# J2-1xGTHQ_L_1xGTHCLK_GTRQ_2xGTRCLK_4xPLL.net
KiCad netlist of a schematic drawn in Altium Designer
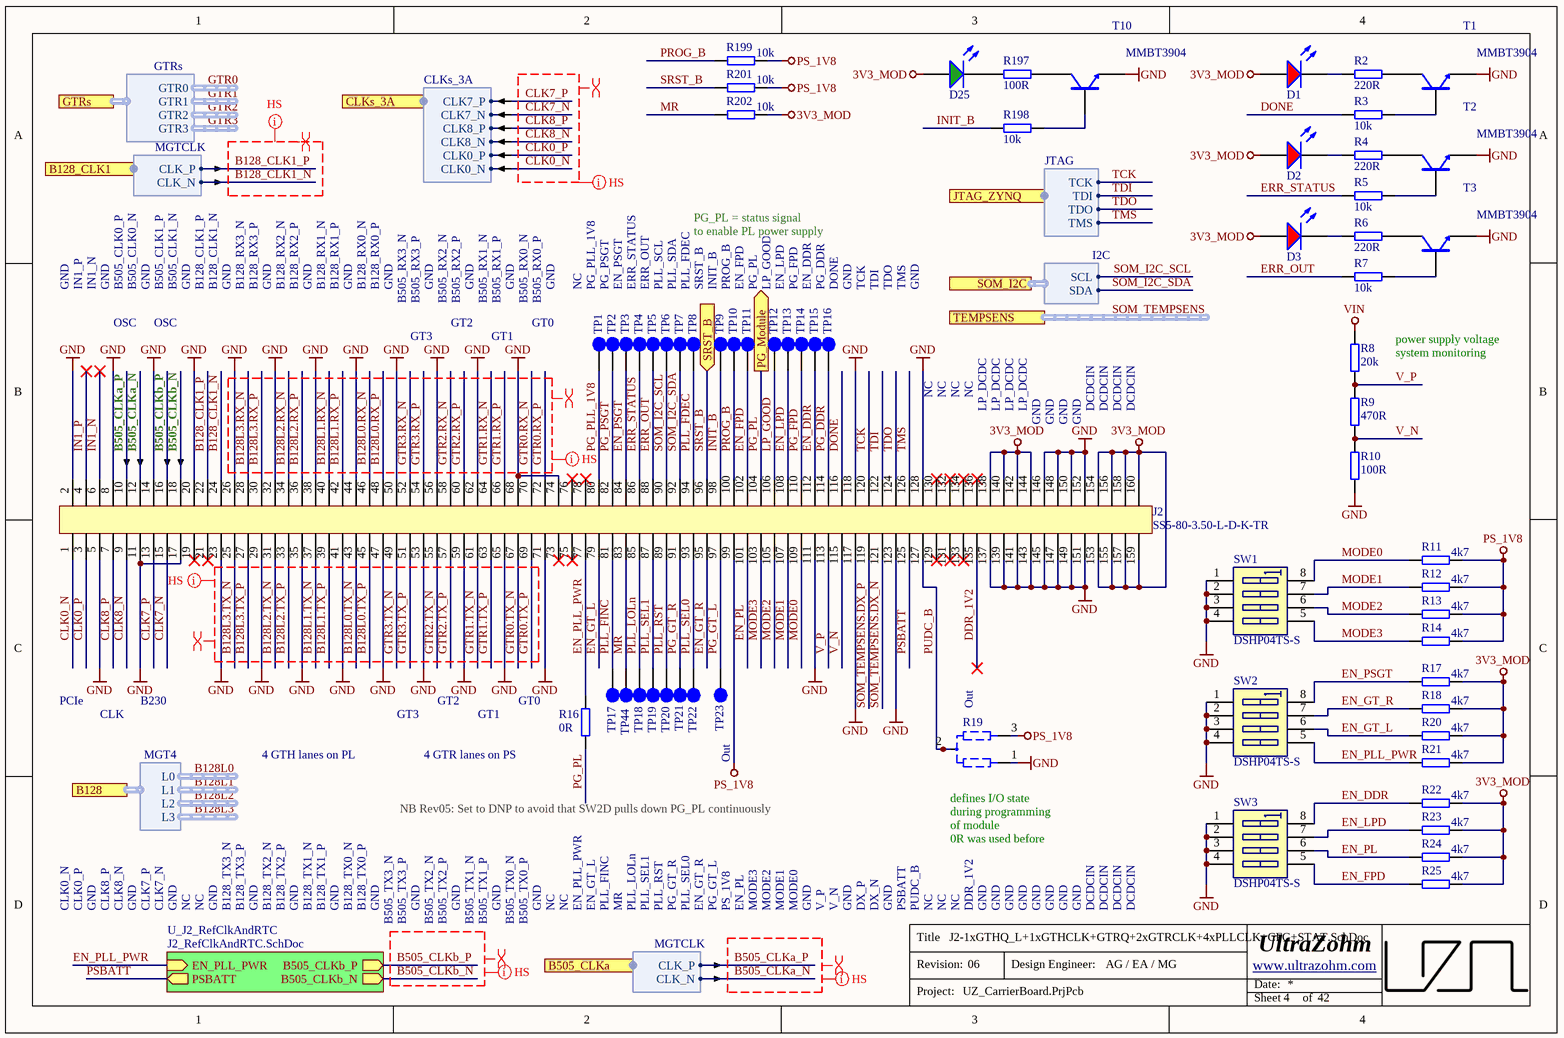
[diagram p0: J2-1xGTHQ_L+1xGTHCLK+GTRQ+2xGTRCLK+4xPLLCLK+CFG+STAT.SchDoc]

(export (version "E")
  (design (tool "Eeschema 10.0.6"))
  (components
    (comp (ref "D1")
      (value "LED Red")
      (footprint "WL-SMCW_0603")
      (description "Standard LEDs - SMD 0603 red")
      (fields
        (field (name "MANUFACTURER PART NUMBER") "UZgen_LED_0603_Red")
        (field (name "MANUFACTURER") "UZgen")
        (field (name "CREATED FROM") "UZgenTool")
      )
      (libsource (lib "user") (part "LED_Red"))
    )
    (comp (ref "D2")
      (value "LED Red")
      (footprint "WL-SMCW_0603")
      (description "Standard LEDs - SMD 0603 red")
      (fields
        (field (name "MANUFACTURER PART NUMBER") "UZgen_LED_0603_Red")
        (field (name "MANUFACTURER") "UZgen")
        (field (name "CREATED FROM") "UZgenTool")
      )
      (libsource (lib "user") (part "LED_Red"))
    )
    (comp (ref "D3")
      (value "LED Red")
      (footprint "WL-SMCW_0603")
      (description "Standard LEDs - SMD 0603 red")
      (fields
        (field (name "MANUFACTURER PART NUMBER") "UZgen_LED_0603_Red")
        (field (name "MANUFACTURER") "UZgen")
        (field (name "CREATED FROM") "UZgenTool")
      )
      (libsource (lib "user") (part "LED_Red"))
    )
    (comp (ref "D25")
      (value "LED Green")
      (footprint "WL-SMCW_0603")
      (description "Standard LEDs - SMD 0603 green")
      (fields
        (field (name "MANUFACTURER PART NUMBER") "UZgen_LED_0603_Green")
        (field (name "MANUFACTURER") "UZgen")
        (field (name "CREATED FROM") "UZgenTool")
      )
      (libsource (lib "user") (part "LED_Green"))
    )
    (comp (ref "J2")
      (value "SS5-80-3.50-L-D-K-TR")
      (footprint "SS5-80-3.50-L-D-K-TR")
      (description "0.5 mm Ultra Fine Pitch Socket REF192552-01, 160 Pins")
      (fields
        (field (name "MANUFACTURER") "SAMTEC")
        (field (name "LCSC PART NUMBER") "C5292077")
        (field (name "CREATED FROM") "MGremer")
      )
      (libsource (lib "user") (part "SS5-80-3.50-L-D-K-TR"))
    )
    (comp (ref "R2")
      (value "220R")
      (footprint "R_0603_TE")
      (description "Generic resistor")
      (fields
        (field (name "TOLERANCE") "1 %")
        (field (name "MANUFACTURER PART NUMBER") "UZgen_R_0603_220R")
        (field (name "CREATED FROM") "UZgenTool")
      )
      (libsource (lib "user") (part "RES"))
    )
    (comp (ref "R3")
      (value "10k")
      (footprint "R_0603_TE")
      (description "Generic resistor")
      (fields
        (field (name "TOLERANCE") "1 %")
        (field (name "MANUFACTURER PART NUMBER") "UZgen_R_0603_10k")
        (field (name "CREATED FROM") "AGeiger")
      )
      (libsource (lib "user") (part "RES"))
    )
    (comp (ref "R4")
      (value "220R")
      (footprint "R_0603_TE")
      (description "Generic resistor")
      (fields
        (field (name "TOLERANCE") "1 %")
        (field (name "MANUFACTURER PART NUMBER") "UZgen_R_0603_220R")
        (field (name "CREATED FROM") "UZgenTool")
      )
      (libsource (lib "user") (part "RES"))
    )
    (comp (ref "R5")
      (value "10k")
      (footprint "R_0603_TE")
      (description "Generic resistor")
      (fields
        (field (name "TOLERANCE") "1 %")
        (field (name "MANUFACTURER PART NUMBER") "UZgen_R_0603_10k")
        (field (name "CREATED FROM") "AGeiger")
      )
      (libsource (lib "user") (part "RES"))
    )
    (comp (ref "R6")
      (value "220R")
      (footprint "R_0603_TE")
      (description "Generic resistor")
      (fields
        (field (name "TOLERANCE") "1 %")
        (field (name "MANUFACTURER PART NUMBER") "UZgen_R_0603_220R")
        (field (name "CREATED FROM") "UZgenTool")
      )
      (libsource (lib "user") (part "RES"))
    )
    (comp (ref "R7")
      (value "10k")
      (footprint "R_0603_TE")
      (description "Generic resistor")
      (fields
        (field (name "TOLERANCE") "1 %")
        (field (name "MANUFACTURER PART NUMBER") "UZgen_R_0603_10k")
        (field (name "CREATED FROM") "AGeiger")
      )
      (libsource (lib "user") (part "RES"))
    )
    (comp (ref "R8")
      (value "20k")
      (footprint "R_0603_TE")
      (description "Generic resistor")
      (fields
        (field (name "TOLERANCE") "1 %")
        (field (name "MANUFACTURER PART NUMBER") "UZgen_R_0603_20k")
        (field (name "CREATED FROM") "UZgenTool")
      )
      (libsource (lib "user") (part "RES"))
    )
    (comp (ref "R9")
      (value "470R")
      (footprint "R_0603_TE")
      (description "Generic resistor")
      (fields
        (field (name "TOLERANCE") "1 %")
        (field (name "MANUFACTURER PART NUMBER") "UZgen_R_0603_470R")
        (field (name "CREATED FROM") "UZgenTool")
      )
      (libsource (lib "user") (part "RES"))
    )
    (comp (ref "R10")
      (value "100R")
      (footprint "R_0603_TE")
      (description "Generic resistor")
      (fields
        (field (name "TOLERANCE") "1 %")
        (field (name "MANUFACTURER PART NUMBER") "UZgen_R_0603_100R")
        (field (name "CREATED FROM") "UZgenTool")
      )
      (libsource (lib "user") (part "RES"))
    )
    (comp (ref "R11")
      (value "4k7")
      (footprint "R_0603_TE")
      (description "Generic resistor")
      (fields
        (field (name "TOLERANCE") "1 %")
        (field (name "MANUFACTURER PART NUMBER") "UZgen_R_0603_4k7")
        (field (name "CREATED FROM") "UZgenTool")
      )
      (libsource (lib "user") (part "RES"))
    )
    (comp (ref "R12")
      (value "4k7")
      (footprint "R_0603_TE")
      (description "Generic resistor")
      (fields
        (field (name "TOLERANCE") "1 %")
        (field (name "MANUFACTURER PART NUMBER") "UZgen_R_0603_4k7")
        (field (name "CREATED FROM") "UZgenTool")
      )
      (libsource (lib "user") (part "RES"))
    )
    (comp (ref "R13")
      (value "4k7")
      (footprint "R_0603_TE")
      (description "Generic resistor")
      (fields
        (field (name "TOLERANCE") "1 %")
        (field (name "MANUFACTURER PART NUMBER") "UZgen_R_0603_4k7")
        (field (name "CREATED FROM") "UZgenTool")
      )
      (libsource (lib "user") (part "RES"))
    )
    (comp (ref "R14")
      (value "4k7")
      (footprint "R_0603_TE")
      (description "Generic resistor")
      (fields
        (field (name "TOLERANCE") "1 %")
        (field (name "MANUFACTURER PART NUMBER") "UZgen_R_0603_4k7")
        (field (name "CREATED FROM") "UZgenTool")
      )
      (libsource (lib "user") (part "RES"))
    )
    (comp (ref "R16")
      (value "0R")
      (footprint "R_0603_TE")
      (description "Generic resistor")
      (fields
        (field (name "TOLERANCE") "1 %")
        (field (name "MANUFACTURER PART NUMBER") "UZgen_R_0603_0R")
        (field (name "CREATED FROM") "UZgenTool")
      )
      (libsource (lib "user") (part "RES"))
    )
    (comp (ref "R17")
      (value "4k7")
      (footprint "R_0603_TE")
      (description "Generic resistor")
      (fields
        (field (name "TOLERANCE") "1 %")
        (field (name "MANUFACTURER PART NUMBER") "UZgen_R_0603_4k7")
        (field (name "CREATED FROM") "UZgenTool")
      )
      (libsource (lib "user") (part "RES"))
    )
    (comp (ref "R18")
      (value "4k7")
      (footprint "R_0603_TE")
      (description "Generic resistor")
      (fields
        (field (name "TOLERANCE") "1 %")
        (field (name "MANUFACTURER PART NUMBER") "UZgen_R_0603_4k7")
        (field (name "CREATED FROM") "UZgenTool")
      )
      (libsource (lib "user") (part "RES"))
    )
    (comp (ref "R19")
      (value "Manual Assembly 1608 (0603)")
      (footprint "TP_DUAL_RES_0603")
      (description "Manual Assembly Resistors Placeholder 1608 (0603) Dual")
      (libsource (lib "TE") (part "TP_DUAL_RES_0603"))
    )
    (comp (ref "R20")
      (value "4k7")
      (footprint "R_0603_TE")
      (description "Generic resistor")
      (fields
        (field (name "TOLERANCE") "1 %")
        (field (name "MANUFACTURER PART NUMBER") "UZgen_R_0603_4k7")
        (field (name "CREATED FROM") "UZgenTool")
      )
      (libsource (lib "user") (part "RES"))
    )
    (comp (ref "R21")
      (value "4k7")
      (footprint "R_0603_TE")
      (description "Generic resistor")
      (fields
        (field (name "TOLERANCE") "1 %")
        (field (name "MANUFACTURER PART NUMBER") "UZgen_R_0603_4k7")
        (field (name "CREATED FROM") "UZgenTool")
      )
      (libsource (lib "user") (part "RES"))
    )
    (comp (ref "R22")
      (value "4k7")
      (footprint "R_0603_TE")
      (description "Generic resistor")
      (fields
        (field (name "TOLERANCE") "1 %")
        (field (name "MANUFACTURER PART NUMBER") "UZgen_R_0603_4k7")
        (field (name "CREATED FROM") "UZgenTool")
      )
      (libsource (lib "user") (part "RES"))
    )
    (comp (ref "R23")
      (value "4k7")
      (footprint "R_0603_TE")
      (description "Generic resistor")
      (fields
        (field (name "TOLERANCE") "1 %")
        (field (name "MANUFACTURER PART NUMBER") "UZgen_R_0603_4k7")
        (field (name "CREATED FROM") "UZgenTool")
      )
      (libsource (lib "user") (part "RES"))
    )
    (comp (ref "R24")
      (value "4k7")
      (footprint "R_0603_TE")
      (description "Generic resistor")
      (fields
        (field (name "TOLERANCE") "1 %")
        (field (name "MANUFACTURER PART NUMBER") "UZgen_R_0603_4k7")
        (field (name "CREATED FROM") "UZgenTool")
      )
      (libsource (lib "user") (part "RES"))
    )
    (comp (ref "R25")
      (value "4k7")
      (footprint "R_0603_TE")
      (description "Generic resistor")
      (fields
        (field (name "TOLERANCE") "1 %")
        (field (name "MANUFACTURER PART NUMBER") "UZgen_R_0603_4k7")
        (field (name "CREATED FROM") "UZgenTool")
      )
      (libsource (lib "user") (part "RES"))
    )
    (comp (ref "R197")
      (value "100R")
      (footprint "R_0603_TE")
      (description "Generic resistor")
      (fields
        (field (name "TOLERANCE") "1 %")
        (field (name "MANUFACTURER PART NUMBER") "UZgen_R_0603_100R")
        (field (name "CREATED FROM") "UZgenTool")
      )
      (libsource (lib "user") (part "RES"))
    )
    (comp (ref "R198")
      (value "10k")
      (footprint "R_0603_TE")
      (description "Generic resistor")
      (fields
        (field (name "TOLERANCE") "1 %")
        (field (name "MANUFACTURER PART NUMBER") "UZgen_R_0603_10k")
        (field (name "CREATED FROM") "AGeiger")
      )
      (libsource (lib "user") (part "RES"))
    )
    (comp (ref "R199")
      (value "10k")
      (footprint "R_0603_TE")
      (description "Generic resistor")
      (fields
        (field (name "TOLERANCE") "1 %")
        (field (name "MANUFACTURER PART NUMBER") "UZgen_R_0603_10k")
        (field (name "CREATED FROM") "AGeiger")
      )
      (libsource (lib "user") (part "RES"))
    )
    (comp (ref "R201")
      (value "10k")
      (footprint "R_0603_TE")
      (description "Generic resistor")
      (fields
        (field (name "TOLERANCE") "1 %")
        (field (name "MANUFACTURER PART NUMBER") "UZgen_R_0603_10k")
        (field (name "CREATED FROM") "AGeiger")
      )
      (libsource (lib "user") (part "RES"))
    )
    (comp (ref "R202")
      (value "10k")
      (footprint "R_0603_TE")
      (description "Generic resistor")
      (fields
        (field (name "TOLERANCE") "1 %")
        (field (name "MANUFACTURER PART NUMBER") "UZgen_R_0603_10k")
        (field (name "CREATED FROM") "AGeiger")
      )
      (libsource (lib "user") (part "RES"))
    )
    (comp (ref "SW1")
      (value "DSHP04TS-S")
      (footprint "416131160804")
      (description "04p, 1.27mm Pitch, Horizontal, HP Type, SMT, flat Actuator, black, with Tape, T&R")
      (fields
        (field (name "MANUFACTURER") "XKB Connectivity")
        (field (name "LCSC PART NUMBER") "C319050")
        (field (name "CREATED FROM") "T. Wendt")
      )
      (libsource (lib "user") (part "DIP-SW-4p"))
    )
    (comp (ref "SW2")
      (value "DSHP04TS-S")
      (footprint "416131160804")
      (description "04p, 1.27mm Pitch, Horizontal, HP Type, SMT, flat Actuator, black, with Tape, T&R")
      (fields
        (field (name "MANUFACTURER") "XKB Connectivity")
        (field (name "LCSC PART NUMBER") "C319050")
        (field (name "CREATED FROM") "T. Wendt")
      )
      (libsource (lib "user") (part "DIP-SW-4p"))
    )
    (comp (ref "SW3")
      (value "DSHP04TS-S")
      (footprint "416131160804")
      (description "04p, 1.27mm Pitch, Horizontal, HP Type, SMT, flat Actuator, black, with Tape, T&R")
      (fields
        (field (name "MANUFACTURER") "XKB Connectivity")
        (field (name "LCSC PART NUMBER") "C319050")
        (field (name "CREATED FROM") "T. Wendt")
      )
      (libsource (lib "user") (part "DIP-SW-4p"))
    )
    (comp (ref "T1")
      (value "MMBT3904")
      (footprint "SOT95P280X145-3N")
      (fields
        (field (name "MANUFACTURER") "Jiangsu Changjing Electronics Technology Co., Ltd.")
        (field (name "LCSC PART NUMBER") "C20526")
        (field (name "CREATED FROM") "NDiringer")
      )
      (libsource (lib "user") (part "NPN-SOT23"))
    )
    (comp (ref "T2")
      (value "MMBT3904")
      (footprint "SOT95P280X145-3N")
      (fields
        (field (name "MANUFACTURER") "Jiangsu Changjing Electronics Technology Co., Ltd.")
        (field (name "LCSC PART NUMBER") "C20526")
        (field (name "CREATED FROM") "NDiringer")
      )
      (libsource (lib "user") (part "NPN-SOT23"))
    )
    (comp (ref "T3")
      (value "MMBT3904")
      (footprint "SOT95P280X145-3N")
      (fields
        (field (name "MANUFACTURER") "Jiangsu Changjing Electronics Technology Co., Ltd.")
        (field (name "LCSC PART NUMBER") "C20526")
        (field (name "CREATED FROM") "NDiringer")
      )
      (libsource (lib "user") (part "NPN-SOT23"))
    )
    (comp (ref "T10")
      (value "MMBT3904")
      (footprint "SOT95P280X145-3N")
      (fields
        (field (name "MANUFACTURER") "Jiangsu Changjing Electronics Technology Co., Ltd.")
        (field (name "LCSC PART NUMBER") "C20526")
        (field (name "CREATED FROM") "NDiringer")
      )
      (libsource (lib "user") (part "NPN-SOT23"))
    )
    (comp (ref "TP1") (value "Testpoint 1mm") (footprint "TP_1mm") (libsource (lib "TE") (part "TP")))
    (comp (ref "TP2") (value "Testpoint 1mm") (footprint "TP_1mm") (libsource (lib "TE") (part "TP")))
    (comp (ref "TP3") (value "Testpoint 1mm") (footprint "TP_1mm") (libsource (lib "TE") (part "TP")))
    (comp (ref "TP4") (value "Testpoint 1mm") (footprint "TP_1mm") (libsource (lib "TE") (part "TP")))
    (comp (ref "TP5") (value "Testpoint 1mm") (footprint "TP_1mm") (libsource (lib "TE") (part "TP")))
    (comp (ref "TP6") (value "Testpoint 1mm") (footprint "TP_1mm") (libsource (lib "TE") (part "TP")))
    (comp (ref "TP7") (value "Testpoint 1mm") (footprint "TP_1mm") (libsource (lib "TE") (part "TP")))
    (comp (ref "TP8") (value "Testpoint 1mm") (footprint "TP_1mm") (libsource (lib "TE") (part "TP")))
    (comp (ref "TP9") (value "Testpoint 1mm") (footprint "TP_1mm") (libsource (lib "TE") (part "TP")))
    (comp (ref "TP10") (value "Testpoint 1mm") (footprint "TP_1mm") (libsource (lib "TE") (part "TP")))
    (comp (ref "TP11") (value "Testpoint 1mm") (footprint "TP_1mm") (libsource (lib "TE") (part "TP")))
    (comp (ref "TP12") (value "Testpoint 1mm") (footprint "TP_1mm") (libsource (lib "TE") (part "TP")))
    (comp (ref "TP13") (value "Testpoint 1mm") (footprint "TP_1mm") (libsource (lib "TE") (part "TP")))
    (comp (ref "TP14") (value "Testpoint 1mm") (footprint "TP_1mm") (libsource (lib "TE") (part "TP")))
    (comp (ref "TP15") (value "Testpoint 1mm") (footprint "TP_1mm") (libsource (lib "TE") (part "TP")))
    (comp (ref "TP16") (value "Testpoint 1mm") (footprint "TP_1mm") (libsource (lib "TE") (part "TP")))
    (comp (ref "TP17") (value "Testpoint 1mm") (footprint "TP_1mm") (libsource (lib "TE") (part "TP")))
    (comp (ref "TP18") (value "Testpoint 1mm") (footprint "TP_1mm") (libsource (lib "TE") (part "TP")))
    (comp (ref "TP19") (value "Testpoint 1mm") (footprint "TP_1mm") (libsource (lib "TE") (part "TP")))
    (comp (ref "TP20") (value "Testpoint 1mm") (footprint "TP_1mm") (libsource (lib "TE") (part "TP")))
    (comp (ref "TP21") (value "Testpoint 1mm") (footprint "TP_1mm") (libsource (lib "TE") (part "TP")))
    (comp (ref "TP22") (value "Testpoint 1mm") (footprint "TP_1mm") (libsource (lib "TE") (part "TP")))
    (comp (ref "TP23") (value "Testpoint 1mm") (footprint "TP_1mm") (libsource (lib "TE") (part "TP")))
    (comp (ref "TP44") (value "Testpoint 1mm") (footprint "TP_1mm") (libsource (lib "TE") (part "TP")))
  )
  (nets
    (net (code "16") (name "/B128L0.RX_N") (class "Default")
      (node (ref "J2") (pin "46") (pinfunction "46_46") (pintype "passive"))
    )
    (net (code "17") (name "/B128L0.RX_P") (class "Default")
      (node (ref "J2") (pin "48") (pinfunction "48_48") (pintype "passive"))
    )
    (net (code "18") (name "/B128L0.TX_N") (class "Default")
      (node (ref "J2") (pin "43") (pinfunction "43_43") (pintype "passive"))
    )
    (net (code "19") (name "/B128L0.TX_P") (class "Default")
      (node (ref "J2") (pin "45") (pinfunction "45_45") (pintype "passive"))
    )
    (net (code "21") (name "/B128L1.RX_N") (class "Default")
      (node (ref "J2") (pin "40") (pinfunction "40_40") (pintype "passive"))
    )
    (net (code "22") (name "/B128L1.RX_P") (class "Default")
      (node (ref "J2") (pin "42") (pinfunction "42_42") (pintype "passive"))
    )
    (net (code "23") (name "/B128L1.TX_N") (class "Default")
      (node (ref "J2") (pin "37") (pinfunction "37_37") (pintype "passive"))
    )
    (net (code "24") (name "/B128L1.TX_P") (class "Default")
      (node (ref "J2") (pin "39") (pinfunction "39_39") (pintype "passive"))
    )
    (net (code "25") (name "/B128L2.RX_N") (class "Default")
      (node (ref "J2") (pin "34") (pinfunction "34_34") (pintype "passive"))
    )
    (net (code "26") (name "/B128L2.RX_P") (class "Default")
      (node (ref "J2") (pin "36") (pinfunction "36_36") (pintype "passive"))
    )
    (net (code "27") (name "/B128L2.TX_N") (class "Default")
      (node (ref "J2") (pin "31") (pinfunction "31_31") (pintype "passive"))
    )
    (net (code "28") (name "/B128L2.TX_P") (class "Default")
      (node (ref "J2") (pin "33") (pinfunction "33_33") (pintype "passive"))
    )
    (net (code "29") (name "/B128L3.RX_N") (class "Default")
      (node (ref "J2") (pin "28") (pinfunction "28_28") (pintype "passive"))
    )
    (net (code "30") (name "/B128L3.RX_P") (class "Default")
      (node (ref "J2") (pin "30") (pinfunction "30_30") (pintype "passive"))
    )
    (net (code "31") (name "/B128L3.TX_N") (class "Default")
      (node (ref "J2") (pin "25") (pinfunction "25_25") (pintype "passive"))
    )
    (net (code "32") (name "/B128L3.TX_P") (class "Default")
      (node (ref "J2") (pin "27") (pinfunction "27_27") (pintype "passive"))
    )
    (net (code "33") (name "/B128_CLK1_N") (class "Default")
      (node (ref "J2") (pin "24") (pinfunction "24_24") (pintype "passive"))
    )
    (net (code "34") (name "/B128_CLK1_P") (class "Default")
      (node (ref "J2") (pin "22") (pinfunction "22_22") (pintype "passive"))
    )
    (net (code "36") (name "/B505_CLKa_N") (class "Default")
      (node (ref "J2") (pin "12") (pinfunction "12_12") (pintype "passive"))
    )
    (net (code "37") (name "/B505_CLKa_P") (class "Default")
      (node (ref "J2") (pin "10") (pinfunction "10_10") (pintype "passive"))
    )
    (net (code "38") (name "/B505_CLKb_N") (class "Default")
      (node (ref "J2") (pin "18") (pinfunction "18_18") (pintype "passive"))
    )
    (net (code "39") (name "/B505_CLKb_P") (class "Default")
      (node (ref "J2") (pin "16") (pinfunction "16_16") (pintype "passive"))
    )
    (net (code "40") (name "/CLK0_N") (class "Default")
      (node (ref "J2") (pin "1") (pinfunction "1_1") (pintype "passive"))
    )
    (net (code "41") (name "/CLK0_P") (class "Default")
      (node (ref "J2") (pin "3") (pinfunction "3_3") (pintype "passive"))
    )
    (net (code "42") (name "/CLK7_N") (class "Default")
      (node (ref "J2") (pin "15") (pinfunction "15_15") (pintype "passive"))
    )
    (net (code "43") (name "/CLK7_P") (class "Default")
      (node (ref "J2") (pin "13") (pinfunction "13_13") (pintype "passive"))
    )
    (net (code "44") (name "/CLK8_N") (class "Default")
      (node (ref "J2") (pin "9") (pinfunction "9_9") (pintype "passive"))
    )
    (net (code "45") (name "/CLK8_P") (class "Default")
      (node (ref "J2") (pin "7") (pinfunction "7_7") (pintype "passive"))
    )
    (net (code "46") (name "/DDR_1V2") (class "Default")
      (node (ref "J2") (pin "135") (pinfunction "135_135") (pintype "passive+no_connect"))
    )
    (net (code "47") (name "/DONE") (class "Default")
      (node (ref "J2") (pin "116") (pinfunction "116_116") (pintype "passive"))
      (node (ref "R3") (pin "1") (pinfunction "1_1") (pintype "passive"))
    )
    (net (code "48") (name "/EN_DDR") (class "Default")
      (node (ref "J2") (pin "112") (pinfunction "112_112") (pintype "passive"))
      (node (ref "R22") (pin "1") (pinfunction "1_1") (pintype "passive"))
      (node (ref "SW3") (pin "8") (pinfunction "8_8") (pintype "passive"))
      (node (ref "TP15") (pin "1") (pintype "passive"))
    )
    (net (code "49") (name "/EN_FPD") (class "Default")
      (node (ref "J2") (pin "102") (pinfunction "102_102") (pintype "passive"))
      (node (ref "R25") (pin "1") (pinfunction "1_1") (pintype "passive"))
      (node (ref "SW3") (pin "5") (pinfunction "5_5") (pintype "passive"))
      (node (ref "TP11") (pin "1") (pintype "passive"))
    )
    (net (code "50") (name "/EN_GT_L") (class "Default")
      (node (ref "J2") (pin "79") (pinfunction "79_79") (pintype "passive"))
      (node (ref "R20") (pin "1") (pinfunction "1_1") (pintype "passive"))
      (node (ref "SW2") (pin "6") (pinfunction "6_6") (pintype "passive"))
    )
    (net (code "51") (name "/EN_GT_R") (class "Default")
      (node (ref "J2") (pin "95") (pinfunction "95_95") (pintype "passive"))
      (node (ref "R18") (pin "1") (pinfunction "1_1") (pintype "passive"))
      (node (ref "SW2") (pin "7") (pinfunction "7_7") (pintype "passive"))
    )
    (net (code "52") (name "/EN_LPD") (class "Default")
      (node (ref "J2") (pin "108") (pinfunction "108_108") (pintype "passive"))
      (node (ref "R23") (pin "1") (pinfunction "1_1") (pintype "passive"))
      (node (ref "SW3") (pin "7") (pinfunction "7_7") (pintype "passive"))
      (node (ref "TP13") (pin "1") (pintype "passive"))
    )
    (net (code "53") (name "/EN_PL") (class "Default")
      (node (ref "J2") (pin "101") (pinfunction "101_101") (pintype "passive"))
      (node (ref "R24") (pin "1") (pinfunction "1_1") (pintype "passive"))
      (node (ref "SW3") (pin "6") (pinfunction "6_6") (pintype "passive"))
    )
    (net (code "54") (name "/EN_PLL_PWR") (class "Default")
      (node (ref "J2") (pin "77") (pinfunction "77_77") (pintype "passive"))
      (node (ref "R16") (pin "2") (pinfunction "2_2") (pintype "passive"))
      (node (ref "R21") (pin "1") (pinfunction "1_1") (pintype "passive"))
      (node (ref "SW2") (pin "5") (pinfunction "5_5") (pintype "passive"))
    )
    (net (code "55") (name "/EN_PSGT") (class "Default")
      (node (ref "J2") (pin "84") (pinfunction "84_84") (pintype "passive"))
      (node (ref "R17") (pin "1") (pinfunction "1_1") (pintype "passive"))
      (node (ref "SW2") (pin "8") (pinfunction "8_8") (pintype "passive"))
      (node (ref "TP3") (pin "1") (pintype "passive"))
    )
    (net (code "56") (name "/ERR_OUT") (class "Default")
      (node (ref "J2") (pin "88") (pinfunction "88_88") (pintype "passive"))
      (node (ref "R7") (pin "1") (pinfunction "1_1") (pintype "passive"))
      (node (ref "TP5") (pin "1") (pintype "passive"))
    )
    (net (code "57") (name "/ERR_STATUS") (class "Default")
      (node (ref "J2") (pin "86") (pinfunction "86_86") (pintype "passive"))
      (node (ref "R5") (pin "1") (pinfunction "1_1") (pintype "passive"))
      (node (ref "TP4") (pin "1") (pintype "passive"))
    )
    (net (code "58") (name "/GTR0.RX_N") (class "Default")
      (node (ref "J2") (pin "70") (pinfunction "70_70") (pintype "passive"))
    )
    (net (code "59") (name "/GTR0.RX_P") (class "Default")
      (node (ref "J2") (pin "72") (pinfunction "72_72") (pintype "passive"))
    )
    (net (code "60") (name "/GTR0.TX_N") (class "Default")
      (node (ref "J2") (pin "67") (pinfunction "67_67") (pintype "passive"))
    )
    (net (code "61") (name "/GTR0.TX_P") (class "Default")
      (node (ref "J2") (pin "69") (pinfunction "69_69") (pintype "passive"))
    )
    (net (code "63") (name "/GTR1.RX_N") (class "Default")
      (node (ref "J2") (pin "64") (pinfunction "64_64") (pintype "passive"))
    )
    (net (code "64") (name "/GTR1.RX_P") (class "Default")
      (node (ref "J2") (pin "66") (pinfunction "66_66") (pintype "passive"))
    )
    (net (code "65") (name "/GTR1.TX_N") (class "Default")
      (node (ref "J2") (pin "61") (pinfunction "61_61") (pintype "passive"))
    )
    (net (code "66") (name "/GTR1.TX_P") (class "Default")
      (node (ref "J2") (pin "63") (pinfunction "63_63") (pintype "passive"))
    )
    (net (code "67") (name "/GTR2.RX_N") (class "Default")
      (node (ref "J2") (pin "58") (pinfunction "58_58") (pintype "passive"))
    )
    (net (code "68") (name "/GTR2.RX_P") (class "Default")
      (node (ref "J2") (pin "60") (pinfunction "60_60") (pintype "passive"))
    )
    (net (code "69") (name "/GTR2.TX_N") (class "Default")
      (node (ref "J2") (pin "55") (pinfunction "55_55") (pintype "passive"))
    )
    (net (code "70") (name "/GTR2.TX_P") (class "Default")
      (node (ref "J2") (pin "57") (pinfunction "57_57") (pintype "passive"))
    )
    (net (code "71") (name "/GTR3.RX_N") (class "Default")
      (node (ref "J2") (pin "52") (pinfunction "52_52") (pintype "passive"))
    )
    (net (code "72") (name "/GTR3.RX_P") (class "Default")
      (node (ref "J2") (pin "54") (pinfunction "54_54") (pintype "passive"))
    )
    (net (code "73") (name "/GTR3.TX_N") (class "Default")
      (node (ref "J2") (pin "49") (pinfunction "49_49") (pintype "passive"))
    )
    (net (code "74") (name "/GTR3.TX_P") (class "Default")
      (node (ref "J2") (pin "51") (pinfunction "51_51") (pintype "passive"))
    )
    (net (code "76") (name "/IN1_N") (class "Default")
      (node (ref "J2") (pin "6") (pinfunction "6_6") (pintype "passive+no_connect"))
    )
    (net (code "77") (name "/IN1_P") (class "Default")
      (node (ref "J2") (pin "4") (pinfunction "4_4") (pintype "passive+no_connect"))
    )
    (net (code "78") (name "/INIT_B") (class "Default")
      (node (ref "J2") (pin "98") (pinfunction "98_98") (pintype "passive"))
      (node (ref "R198") (pin "1") (pinfunction "1_1") (pintype "passive"))
      (node (ref "TP9") (pin "1") (pintype "passive"))
    )
    (net (code "79") (name "/LP_GOOD") (class "Default")
      (node (ref "J2") (pin "106") (pinfunction "106_106") (pintype "passive"))
      (node (ref "TP12") (pin "1") (pintype "passive"))
    )
    (net (code "80") (name "/MODE0") (class "Default")
      (node (ref "J2") (pin "109") (pinfunction "109_109") (pintype "passive"))
      (node (ref "R11") (pin "1") (pinfunction "1_1") (pintype "passive"))
      (node (ref "SW1") (pin "8") (pinfunction "8_8") (pintype "passive"))
    )
    (net (code "81") (name "/MODE1") (class "Default")
      (node (ref "J2") (pin "107") (pinfunction "107_107") (pintype "passive"))
      (node (ref "R12") (pin "1") (pinfunction "1_1") (pintype "passive"))
      (node (ref "SW1") (pin "7") (pinfunction "7_7") (pintype "passive"))
    )
    (net (code "82") (name "/MODE2") (class "Default")
      (node (ref "J2") (pin "105") (pinfunction "105_105") (pintype "passive"))
      (node (ref "R13") (pin "1") (pinfunction "1_1") (pintype "passive"))
      (node (ref "SW1") (pin "6") (pinfunction "6_6") (pintype "passive"))
    )
    (net (code "83") (name "/MODE3") (class "Default")
      (node (ref "J2") (pin "103") (pinfunction "103_103") (pintype "passive"))
      (node (ref "R14") (pin "1") (pinfunction "1_1") (pintype "passive"))
      (node (ref "SW1") (pin "5") (pinfunction "5_5") (pintype "passive"))
    )
    (net (code "84") (name "/MR") (class "Default")
      (node (ref "J2") (pin "83") (pinfunction "83_83") (pintype "passive"))
      (node (ref "R202") (pin "1") (pinfunction "1_1") (pintype "passive"))
      (node (ref "TP44") (pin "1") (pintype "passive"))
    )
    (net (code "85") (name "/PG_DDR") (class "Default")
      (node (ref "J2") (pin "114") (pinfunction "114_114") (pintype "passive"))
      (node (ref "TP16") (pin "1") (pintype "passive"))
    )
    (net (code "86") (name "/PG_FPD") (class "Default")
      (node (ref "J2") (pin "110") (pinfunction "110_110") (pintype "passive"))
      (node (ref "TP14") (pin "1") (pintype "passive"))
    )
    (net (code "87") (name "/PG_GT_L") (class "Default")
      (node (ref "J2") (pin "97") (pinfunction "97_97") (pintype "passive"))
      (node (ref "TP23") (pin "1") (pintype "passive"))
    )
    (net (code "88") (name "/PG_GT_R") (class "Default")
      (node (ref "J2") (pin "91") (pinfunction "91_91") (pintype "passive"))
      (node (ref "TP21") (pin "1") (pintype "passive"))
    )
    (net (code "89") (name "/PG_PL") (class "Default")
      (node (ref "J2") (pin "104") (pinfunction "104_104") (pintype "passive"))
      (node (ref "R16") (pin "1") (pinfunction "1_1") (pintype "passive"))
    )
    (net (code "90") (name "/PG_PLL_1V8") (class "Default")
      (node (ref "J2") (pin "80") (pinfunction "80_80") (pintype "passive"))
      (node (ref "TP1") (pin "1") (pintype "passive"))
    )
    (net (code "91") (name "/PG_PSGT") (class "Default")
      (node (ref "J2") (pin "82") (pinfunction "82_82") (pintype "passive"))
      (node (ref "TP2") (pin "1") (pintype "passive"))
    )
    (net (code "92") (name "/PLL_FDEC") (class "Default")
      (node (ref "J2") (pin "94") (pinfunction "94_94") (pintype "passive"))
      (node (ref "TP8") (pin "1") (pintype "passive"))
    )
    (net (code "93") (name "/PLL_FINC") (class "Default")
      (node (ref "J2") (pin "81") (pinfunction "81_81") (pintype "passive"))
      (node (ref "TP17") (pin "1") (pintype "passive"))
    )
    (net (code "94") (name "/PLL_LOLn") (class "Default")
      (node (ref "J2") (pin "85") (pinfunction "85_85") (pintype "passive"))
      (node (ref "TP18") (pin "1") (pintype "passive"))
    )
    (net (code "95") (name "/PLL_RST") (class "Default")
      (node (ref "J2") (pin "89") (pinfunction "89_89") (pintype "passive"))
      (node (ref "TP20") (pin "1") (pintype "passive"))
    )
    (net (code "96") (name "/PLL_SEL0") (class "Default")
      (node (ref "J2") (pin "93") (pinfunction "93_93") (pintype "passive"))
      (node (ref "TP22") (pin "1") (pintype "passive"))
    )
    (net (code "97") (name "/PLL_SEL1") (class "Default")
      (node (ref "J2") (pin "87") (pinfunction "87_87") (pintype "passive"))
      (node (ref "TP19") (pin "1") (pintype "passive"))
    )
    (net (code "98") (name "/PROG_B") (class "Default")
      (node (ref "J2") (pin "100") (pinfunction "100_100") (pintype "passive"))
      (node (ref "R199") (pin "1") (pinfunction "1_1") (pintype "passive"))
      (node (ref "TP10") (pin "1") (pintype "passive"))
    )
    (net (code "99") (name "/PSBATT") (class "Default")
      (node (ref "J2") (pin "125") (pinfunction "125_125") (pintype "passive"))
    )
    (net (code "100") (name "/PUDC_B") (class "Default")
      (node (ref "J2") (pin "127") (pinfunction "127_127") (pintype "passive"))
      (node (ref "R19") (pin "2") (pinfunction "2_2") (pintype "passive"))
    )
    (net (code "101") (name "/SOM_I2C_SCL") (class "Default")
      (node (ref "J2") (pin "90") (pinfunction "90_90") (pintype "passive"))
      (node (ref "TP6") (pin "1") (pintype "passive"))
    )
    (net (code "102") (name "/SOM_I2C_SDA") (class "Default")
      (node (ref "J2") (pin "92") (pinfunction "92_92") (pintype "passive"))
      (node (ref "TP7") (pin "1") (pintype "passive"))
    )
    (net (code "103") (name "/SOM_TEMPSENS.DX_N") (class "Default")
      (node (ref "J2") (pin "121") (pinfunction "121_121") (pintype "passive"))
    )
    (net (code "104") (name "/SOM_TEMPSENS.DX_P") (class "Default")
      (node (ref "J2") (pin "119") (pinfunction "119_119") (pintype "passive"))
    )
    (net (code "105") (name "/SRST_B") (class "Default")
      (node (ref "J2") (pin "96") (pinfunction "96_96") (pintype "passive"))
      (node (ref "R201") (pin "1") (pinfunction "1_1") (pintype "passive"))
    )
    (net (code "106") (name "/TCK") (class "Default")
      (node (ref "J2") (pin "120") (pinfunction "120_120") (pintype "passive"))
    )
    (net (code "107") (name "/TDI") (class "Default")
      (node (ref "J2") (pin "122") (pinfunction "122_122") (pintype "passive"))
    )
    (net (code "108") (name "/TDO") (class "Default")
      (node (ref "J2") (pin "124") (pinfunction "124_124") (pintype "passive"))
    )
    (net (code "109") (name "/TMS") (class "Default")
      (node (ref "J2") (pin "126") (pinfunction "126_126") (pintype "passive"))
    )
    (net (code "110") (name "/V_N") (class "Default")
      (node (ref "J2") (pin "115") (pinfunction "115_115") (pintype "passive"))
      (node (ref "R10") (pin "2") (pinfunction "2_2") (pintype "passive"))
      (node (ref "R9") (pin "1") (pinfunction "1_1") (pintype "passive"))
    )
    (net (code "111") (name "/V_P") (class "Default")
      (node (ref "J2") (pin "113") (pinfunction "113_113") (pintype "passive"))
      (node (ref "R8") (pin "1") (pinfunction "1_1") (pintype "passive"))
      (node (ref "R9") (pin "2") (pinfunction "2_2") (pintype "passive"))
    )
    (net (code "123") (name "3V3_MOD") (class "Default")
      (node (ref "D1") (pin "2") (pinfunction "A_2") (pintype "passive"))
      (node (ref "D2") (pin "2") (pinfunction "A_2") (pintype "passive"))
      (node (ref "D25") (pin "2") (pinfunction "A_2") (pintype "passive"))
      (node (ref "D3") (pin "2") (pinfunction "A_2") (pintype "passive"))
      (node (ref "J2") (pin "138") (pinfunction "138_138") (pintype "passive"))
      (node (ref "J2") (pin "140") (pinfunction "140_140") (pintype "passive"))
      (node (ref "J2") (pin "142") (pinfunction "142_142") (pintype "passive"))
      (node (ref "J2") (pin "144") (pinfunction "144_144") (pintype "passive"))
      (node (ref "J2") (pin "153") (pinfunction "153_153") (pintype "passive"))
      (node (ref "J2") (pin "154") (pinfunction "154_154") (pintype "passive"))
      (node (ref "J2") (pin "155") (pinfunction "155_155") (pintype "passive"))
      (node (ref "J2") (pin "156") (pinfunction "156_156") (pintype "passive"))
      (node (ref "J2") (pin "157") (pinfunction "157_157") (pintype "passive"))
      (node (ref "J2") (pin "158") (pinfunction "158_158") (pintype "passive"))
      (node (ref "J2") (pin "159") (pinfunction "159_159") (pintype "passive"))
      (node (ref "J2") (pin "160") (pinfunction "160_160") (pintype "passive"))
      (node (ref "R17") (pin "2") (pinfunction "2_2") (pintype "passive"))
      (node (ref "R18") (pin "2") (pinfunction "2_2") (pintype "passive"))
      (node (ref "R20") (pin "2") (pinfunction "2_2") (pintype "passive"))
      (node (ref "R202") (pin "2") (pinfunction "2_2") (pintype "passive"))
      (node (ref "R21") (pin "2") (pinfunction "2_2") (pintype "passive"))
      (node (ref "R22") (pin "2") (pinfunction "2_2") (pintype "passive"))
      (node (ref "R23") (pin "2") (pinfunction "2_2") (pintype "passive"))
      (node (ref "R24") (pin "2") (pinfunction "2_2") (pintype "passive"))
      (node (ref "R25") (pin "2") (pinfunction "2_2") (pintype "passive"))
    )
    (net (code "124") (name "GND") (class "Default")
      (node (ref "J2") (pin "11") (pinfunction "11_11") (pintype "passive"))
      (node (ref "J2") (pin "111") (pinfunction "111_111") (pintype "passive"))
      (node (ref "J2") (pin "117") (pinfunction "117_117") (pintype "passive"))
      (node (ref "J2") (pin "118") (pinfunction "118_118") (pintype "passive"))
      (node (ref "J2") (pin "123") (pinfunction "123_123") (pintype "passive"))
      (node (ref "J2") (pin "128") (pinfunction "128_128") (pintype "passive"))
      (node (ref "J2") (pin "137") (pinfunction "137_137") (pintype "passive"))
      (node (ref "J2") (pin "139") (pinfunction "139_139") (pintype "passive"))
      (node (ref "J2") (pin "14") (pinfunction "14_14") (pintype "passive"))
      (node (ref "J2") (pin "141") (pinfunction "141_141") (pintype "passive"))
      (node (ref "J2") (pin "143") (pinfunction "143_143") (pintype "passive"))
      (node (ref "J2") (pin "145") (pinfunction "145_145") (pintype "passive"))
      (node (ref "J2") (pin "146") (pinfunction "146_146") (pintype "passive"))
      (node (ref "J2") (pin "147") (pinfunction "147_147") (pintype "passive"))
      (node (ref "J2") (pin "148") (pinfunction "148_148") (pintype "passive"))
      (node (ref "J2") (pin "149") (pinfunction "149_149") (pintype "passive"))
      (node (ref "J2") (pin "150") (pinfunction "150_150") (pintype "passive"))
      (node (ref "J2") (pin "151") (pinfunction "151_151") (pintype "passive"))
      (node (ref "J2") (pin "152") (pinfunction "152_152") (pintype "passive"))
      (node (ref "J2") (pin "17") (pinfunction "17_17") (pintype "passive"))
      (node (ref "J2") (pin "2") (pinfunction "2_2") (pintype "passive"))
      (node (ref "J2") (pin "20") (pinfunction "20_20") (pintype "passive"))
      (node (ref "J2") (pin "23") (pinfunction "23_23") (pintype "passive"))
      (node (ref "J2") (pin "26") (pinfunction "26_26") (pintype "passive"))
      (node (ref "J2") (pin "29") (pinfunction "29_29") (pintype "passive"))
      (node (ref "J2") (pin "32") (pinfunction "32_32") (pintype "passive"))
      (node (ref "J2") (pin "35") (pinfunction "35_35") (pintype "passive"))
      (node (ref "J2") (pin "38") (pinfunction "38_38") (pintype "passive"))
      (node (ref "J2") (pin "41") (pinfunction "41_41") (pintype "passive"))
      (node (ref "J2") (pin "44") (pinfunction "44_44") (pintype "passive"))
      (node (ref "J2") (pin "47") (pinfunction "47_47") (pintype "passive"))
      (node (ref "J2") (pin "5") (pinfunction "5_5") (pintype "passive"))
      (node (ref "J2") (pin "50") (pinfunction "50_50") (pintype "passive"))
      (node (ref "J2") (pin "53") (pinfunction "53_53") (pintype "passive"))
      (node (ref "J2") (pin "56") (pinfunction "56_56") (pintype "passive"))
      (node (ref "J2") (pin "59") (pinfunction "59_59") (pintype "passive"))
      (node (ref "J2") (pin "62") (pinfunction "62_62") (pintype "passive"))
      (node (ref "J2") (pin "65") (pinfunction "65_65") (pintype "passive"))
      (node (ref "J2") (pin "68") (pinfunction "68_68") (pintype "passive"))
      (node (ref "J2") (pin "71") (pinfunction "71_71") (pintype "passive"))
      (node (ref "J2") (pin "74") (pinfunction "74_74") (pintype "passive"))
      (node (ref "J2") (pin "8") (pinfunction "8_8") (pintype "passive"))
      (node (ref "R10") (pin "1") (pinfunction "1_1") (pintype "passive"))
      (node (ref "R19") (pin "1") (pinfunction "1_1") (pintype "passive"))
      (node (ref "SW1") (pin "1") (pinfunction "1_1") (pintype "passive"))
      (node (ref "SW1") (pin "2") (pinfunction "2_2") (pintype "passive"))
      (node (ref "SW1") (pin "3") (pinfunction "3_3") (pintype "passive"))
      (node (ref "SW1") (pin "4") (pinfunction "4_4") (pintype "passive"))
      (node (ref "SW2") (pin "1") (pinfunction "1_1") (pintype "passive"))
      (node (ref "SW2") (pin "2") (pinfunction "2_2") (pintype "passive"))
      (node (ref "SW2") (pin "3") (pinfunction "3_3") (pintype "passive"))
      (node (ref "SW2") (pin "4") (pinfunction "4_4") (pintype "passive"))
      (node (ref "SW3") (pin "1") (pinfunction "1_1") (pintype "passive"))
      (node (ref "SW3") (pin "2") (pinfunction "2_2") (pintype "passive"))
      (node (ref "SW3") (pin "3") (pinfunction "3_3") (pintype "passive"))
      (node (ref "SW3") (pin "4") (pinfunction "4_4") (pintype "passive"))
      (node (ref "T1") (pin "2") (pinfunction "EMITTER_2") (pintype "passive"))
      (node (ref "T10") (pin "2") (pinfunction "EMITTER_2") (pintype "passive"))
      (node (ref "T2") (pin "2") (pinfunction "EMITTER_2") (pintype "passive"))
      (node (ref "T3") (pin "2") (pinfunction "EMITTER_2") (pintype "passive"))
    )
    (net (code "125") (name "Net-(D1-K)") (class "Default")
      (node (ref "D1") (pin "1") (pinfunction "K_1") (pintype "passive"))
      (node (ref "R2") (pin "1") (pinfunction "1_1") (pintype "passive"))
    )
    (net (code "126") (name "Net-(D2-K)") (class "Default")
      (node (ref "D2") (pin "1") (pinfunction "K_1") (pintype "passive"))
      (node (ref "R4") (pin "1") (pinfunction "1_1") (pintype "passive"))
    )
    (net (code "127") (name "Net-(D3-K)") (class "Default")
      (node (ref "D3") (pin "1") (pinfunction "K_1") (pintype "passive"))
      (node (ref "R6") (pin "1") (pinfunction "1_1") (pintype "passive"))
    )
    (net (code "128") (name "Net-(D25-K)") (class "Default")
      (node (ref "D25") (pin "1") (pinfunction "K_1") (pintype "passive"))
      (node (ref "R197") (pin "2") (pinfunction "2_2") (pintype "passive"))
    )
    (net (code "129") (name "Net-(T1-BASIS)") (class "Default")
      (node (ref "R3") (pin "2") (pinfunction "2_2") (pintype "passive"))
      (node (ref "T1") (pin "1") (pinfunction "BASIS_1") (pintype "passive"))
    )
    (net (code "130") (name "Net-(T1-COLLECTOR)") (class "Default")
      (node (ref "R2") (pin "2") (pinfunction "2_2") (pintype "passive"))
      (node (ref "T1") (pin "3") (pinfunction "COLLECTOR_3") (pintype "passive"))
    )
    (net (code "131") (name "Net-(T2-BASIS)") (class "Default")
      (node (ref "R5") (pin "2") (pinfunction "2_2") (pintype "passive"))
      (node (ref "T2") (pin "1") (pinfunction "BASIS_1") (pintype "passive"))
    )
    (net (code "132") (name "Net-(T2-COLLECTOR)") (class "Default")
      (node (ref "R4") (pin "2") (pinfunction "2_2") (pintype "passive"))
      (node (ref "T2") (pin "3") (pinfunction "COLLECTOR_3") (pintype "passive"))
    )
    (net (code "133") (name "Net-(T3-BASIS)") (class "Default")
      (node (ref "R7") (pin "2") (pinfunction "2_2") (pintype "passive"))
      (node (ref "T3") (pin "1") (pinfunction "BASIS_1") (pintype "passive"))
    )
    (net (code "134") (name "Net-(T3-COLLECTOR)") (class "Default")
      (node (ref "R6") (pin "2") (pinfunction "2_2") (pintype "passive"))
      (node (ref "T3") (pin "3") (pinfunction "COLLECTOR_3") (pintype "passive"))
    )
    (net (code "135") (name "Net-(T10-BASIS)") (class "Default")
      (node (ref "R198") (pin "2") (pinfunction "2_2") (pintype "passive"))
      (node (ref "T10") (pin "1") (pinfunction "BASIS_1") (pintype "passive"))
    )
    (net (code "136") (name "Net-(T10-COLLECTOR)") (class "Default")
      (node (ref "R197") (pin "1") (pinfunction "1_1") (pintype "passive"))
      (node (ref "T10") (pin "3") (pinfunction "COLLECTOR_3") (pintype "passive"))
    )
    (net (code "137") (name "PS_1V8") (class "Default")
      (node (ref "J2") (pin "99") (pinfunction "99_99") (pintype "passive"))
      (node (ref "R11") (pin "2") (pinfunction "2_2") (pintype "passive"))
      (node (ref "R12") (pin "2") (pinfunction "2_2") (pintype "passive"))
      (node (ref "R13") (pin "2") (pinfunction "2_2") (pintype "passive"))
      (node (ref "R14") (pin "2") (pinfunction "2_2") (pintype "passive"))
      (node (ref "R19") (pin "3") (pinfunction "3_3") (pintype "passive"))
      (node (ref "R199") (pin "2") (pinfunction "2_2") (pintype "passive"))
      (node (ref "R201") (pin "2") (pinfunction "2_2") (pintype "passive"))
    )
    (net (code "138") (name "VIN") (class "Default")
      (node (ref "R8") (pin "2") (pinfunction "2_2") (pintype "passive"))
    )
    (net (code "139") (name "unconnected-(J2-Pad19)") (class "Default")
      (node (ref "J2") (pin "19") (pinfunction "19_19") (pintype "passive+no_connect"))
    )
    (net (code "140") (name "unconnected-(J2-Pad21)") (class "Default")
      (node (ref "J2") (pin "21") (pinfunction "21_21") (pintype "passive+no_connect"))
    )
    (net (code "141") (name "unconnected-(J2-Pad73)") (class "Default")
      (node (ref "J2") (pin "73") (pinfunction "73_73") (pintype "passive+no_connect"))
    )
    (net (code "142") (name "unconnected-(J2-Pad75)") (class "Default")
      (node (ref "J2") (pin "75") (pinfunction "75_75") (pintype "passive+no_connect"))
    )
    (net (code "143") (name "unconnected-(J2-Pad76)") (class "Default")
      (node (ref "J2") (pin "76") (pinfunction "76_76") (pintype "passive+no_connect"))
    )
    (net (code "144") (name "unconnected-(J2-Pad78)") (class "Default")
      (node (ref "J2") (pin "78") (pinfunction "78_78") (pintype "passive+no_connect"))
    )
    (net (code "145") (name "unconnected-(J2-Pad129)") (class "Default")
      (node (ref "J2") (pin "129") (pinfunction "129_129") (pintype "passive+no_connect"))
    )
    (net (code "146") (name "unconnected-(J2-Pad130)") (class "Default")
      (node (ref "J2") (pin "130") (pinfunction "130_130") (pintype "passive+no_connect"))
    )
    (net (code "147") (name "unconnected-(J2-Pad131)") (class "Default")
      (node (ref "J2") (pin "131") (pinfunction "131_131") (pintype "passive+no_connect"))
    )
    (net (code "148") (name "unconnected-(J2-Pad132)") (class "Default")
      (node (ref "J2") (pin "132") (pinfunction "132_132") (pintype "passive+no_connect"))
    )
    (net (code "149") (name "unconnected-(J2-Pad133)") (class "Default")
      (node (ref "J2") (pin "133") (pinfunction "133_133") (pintype "passive+no_connect"))
    )
    (net (code "150") (name "unconnected-(J2-Pad134)") (class "Default")
      (node (ref "J2") (pin "134") (pinfunction "134_134") (pintype "passive+no_connect"))
    )
    (net (code "151") (name "unconnected-(J2-Pad136)") (class "Default")
      (node (ref "J2") (pin "136") (pinfunction "136_136") (pintype "passive+no_connect"))
    )
  )
)
